# 0.net
KiCad netlist of a schematic drawn in Altium Designer
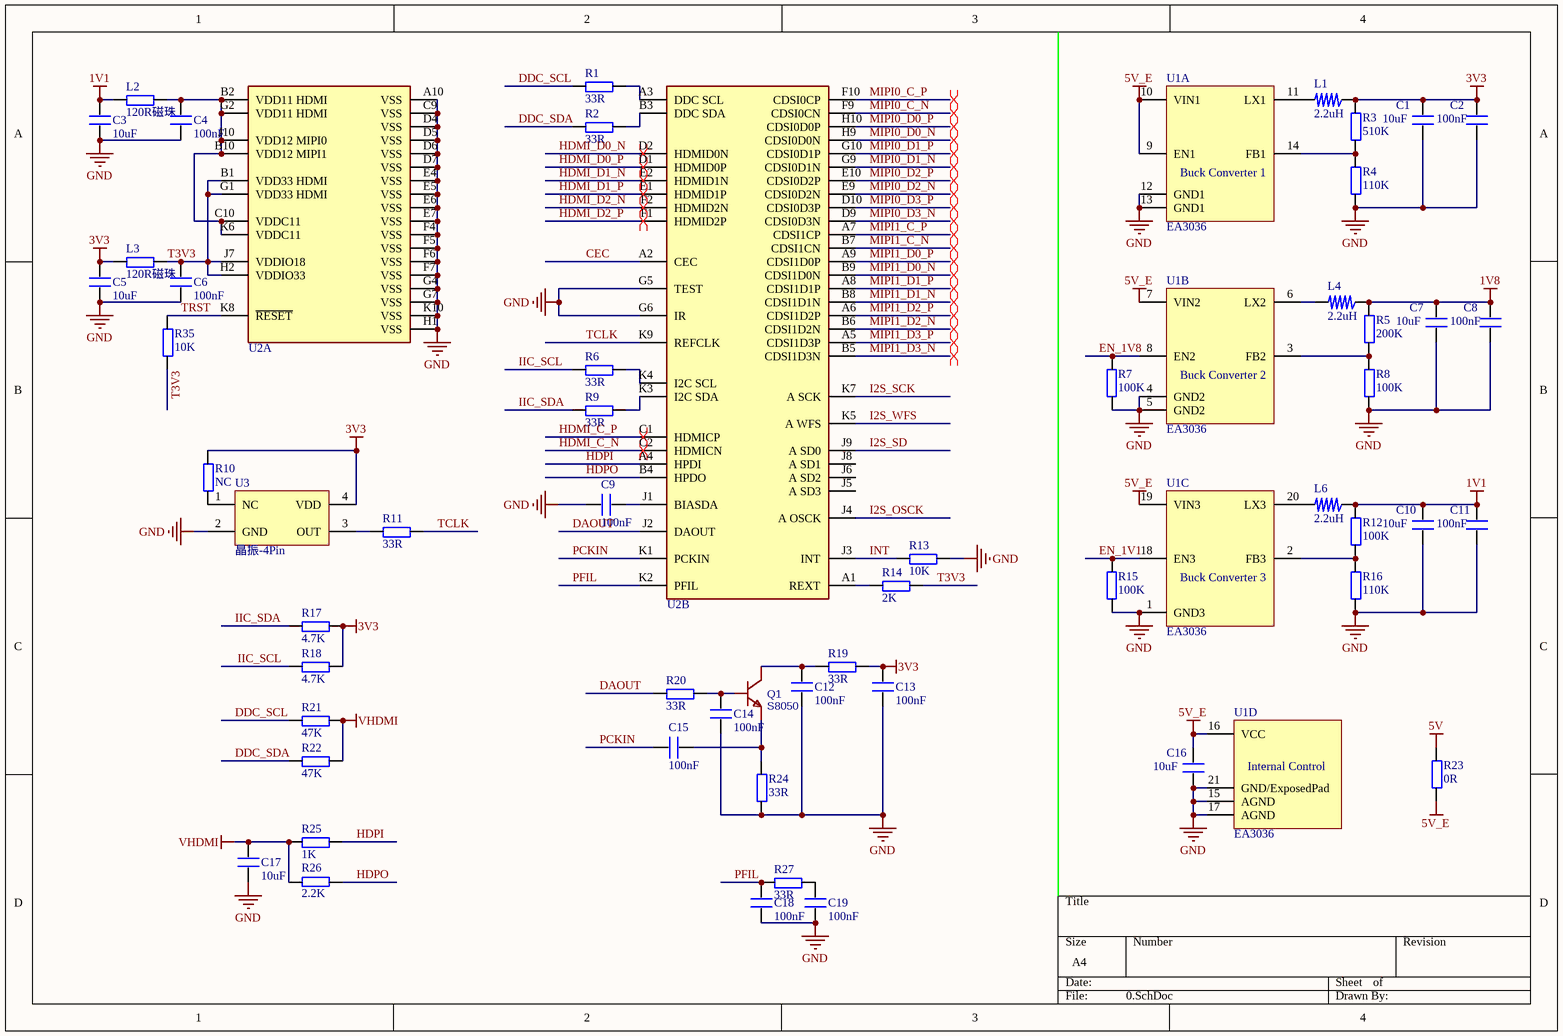
[diagram p0: 0.SchDoc]

(export (version "E")
  (design (tool "Eeschema 10.0.6"))
  (components
    (comp (ref "C1") (value "10uF") (footprint "0603_CAP") (libsource (lib "STM32F429核心板封装库") (part "C")))
    (comp (ref "C2") (value "100nF") (footprint "0603_CAP") (libsource (lib "STM32F429核心板封装库") (part "C")))
    (comp (ref "C3") (value "10uF") (footprint "0603_CAP") (libsource (lib "阿波罗STM32F4&F7底板封装库") (part "C")))
    (comp (ref "C4") (value "100nF") (footprint "0603_CAP") (libsource (lib "阿波罗STM32F4&F7底板封装库") (part "C")))
    (comp (ref "C5") (value "10uF") (footprint "0603_CAP") (libsource (lib "阿波罗STM32F4&F7底板封装库") (part "C")))
    (comp (ref "C6") (value "100nF") (footprint "0603_CAP") (libsource (lib "阿波罗STM32F4&F7底板封装库") (part "C")))
    (comp (ref "C7") (value "10uF") (footprint "0603_CAP") (libsource (lib "STM32F429核心板封装库") (part "C")))
    (comp (ref "C8") (value "100nF") (footprint "0603_CAP") (libsource (lib "STM32F429核心板封装库") (part "C")))
    (comp (ref "C9") (value "100nF") (footprint "0603_CAP") (libsource (lib "阿波罗STM32F4&F7底板封装库") (part "C")))
    (comp (ref "C10") (value "10uF") (footprint "0603_CAP") (libsource (lib "STM32F429核心板封装库") (part "C")))
    (comp (ref "C11") (value "100nF") (footprint "0603_CAP") (libsource (lib "STM32F429核心板封装库") (part "C")))
    (comp (ref "C12")
      (value "100nF")
      (footprint "0603_CAP")
      (libsource (lib "阿波罗STM32F4&F7底板封装库") (part "C"))
    )
    (comp (ref "C13")
      (value "100nF")
      (footprint "0603_CAP")
      (libsource (lib "阿波罗STM32F4&F7底板封装库") (part "C"))
    )
    (comp (ref "C14")
      (value "100nF")
      (footprint "0603_CAP")
      (libsource (lib "阿波罗STM32F4&F7底板封装库") (part "C"))
    )
    (comp (ref "C15")
      (value "100nF")
      (footprint "0603_CAP")
      (libsource (lib "阿波罗STM32F4&F7底板封装库") (part "C"))
    )
    (comp (ref "C16") (value "10uF") (footprint "0603_CAP") (libsource (lib "STM32F429核心板封装库") (part "C")))
    (comp (ref "C17") (value "10uF") (footprint "0603_CAP") (libsource (lib "阿波罗STM32F4&F7底板封装库") (part "C")))
    (comp (ref "C18")
      (value "100nF")
      (footprint "0603_CAP")
      (libsource (lib "阿波罗STM32F4&F7底板封装库") (part "C"))
    )
    (comp (ref "C19")
      (value "100nF")
      (footprint "0603_CAP")
      (libsource (lib "阿波罗STM32F4&F7底板封装库") (part "C"))
    )
    (comp (ref "L1")
      (value "2.2uH")
      (footprint "2520-L")
      (libsource (lib "阿波罗STM32F4&F7底板封装库") (part "L_SOP"))
    )
    (comp (ref "L2") (value "120R磁珠") (footprint "0603_RES") (libsource (lib "STM32F429核心板封装库") (part "R")))
    (comp (ref "L3") (value "120R磁珠") (footprint "0603_RES") (libsource (lib "STM32F429核心板封装库") (part "R")))
    (comp (ref "L4")
      (value "2.2uH")
      (footprint "2520-L")
      (libsource (lib "阿波罗STM32F4&F7底板封装库") (part "L_SOP"))
    )
    (comp (ref "L6")
      (value "2.2uH")
      (footprint "2520-L")
      (libsource (lib "阿波罗STM32F4&F7底板封装库") (part "L_SOP"))
    )
    (comp (ref "Q1")
      (value "S8050")
      (footprint "SOT-23-3_L2.9-W1.3-P1.90-LS2.4-BR")
      (fields (field (name "BOM_SUPPLIER PART") "C779775") (field (name "CONTRIBUTOR") "LCSC"))
      (libsource (lib "altium-import") (part "root_0_S8050_C779775_"))
    )
    (comp (ref "R1") (value "33R") (footprint "0603_RES") (libsource (lib "STM32F429核心板封装库") (part "R")))
    (comp (ref "R2") (value "33R") (footprint "0603_RES") (libsource (lib "STM32F429核心板封装库") (part "R")))
    (comp (ref "R3") (value "510K") (footprint "0603_RES") (libsource (lib "STM32F429核心板封装库") (part "R")))
    (comp (ref "R4") (value "110K") (footprint "0603_RES") (libsource (lib "STM32F429核心板封装库") (part "R")))
    (comp (ref "R5") (value "200K") (footprint "0603_RES") (libsource (lib "STM32F429核心板封装库") (part "R")))
    (comp (ref "R6") (value "33R") (footprint "0603_RES") (libsource (lib "STM32F429核心板封装库") (part "R")))
    (comp (ref "R7") (value "100K") (footprint "0603_RES") (libsource (lib "STM32F429核心板封装库") (part "R")))
    (comp (ref "R8") (value "100K") (footprint "0603_RES") (libsource (lib "STM32F429核心板封装库") (part "R")))
    (comp (ref "R9") (value "33R") (footprint "0603_RES") (libsource (lib "STM32F429核心板封装库") (part "R")))
    (comp (ref "R10") (value "NC") (footprint "0603_RES") (libsource (lib "STM32F429核心板封装库") (part "R")))
    (comp (ref "R11") (value "33R") (footprint "0603_RES") (libsource (lib "STM32F429核心板封装库") (part "R")))
    (comp (ref "R12") (value "100K") (footprint "0603_RES") (libsource (lib "STM32F429核心板封装库") (part "R")))
    (comp (ref "R13") (value "10K") (footprint "0603_RES") (libsource (lib "STM32F429核心板封装库") (part "R")))
    (comp (ref "R14") (value "2K") (footprint "0603_RES") (libsource (lib "STM32F429核心板封装库") (part "R")))
    (comp (ref "R15") (value "100K") (footprint "0603_RES") (libsource (lib "STM32F429核心板封装库") (part "R")))
    (comp (ref "R16") (value "110K") (footprint "0603_RES") (libsource (lib "STM32F429核心板封装库") (part "R")))
    (comp (ref "R17") (value "4.7K") (footprint "0603_RES") (libsource (lib "STM32F429核心板封装库") (part "R")))
    (comp (ref "R18") (value "4.7K") (footprint "0603_RES") (libsource (lib "STM32F429核心板封装库") (part "R")))
    (comp (ref "R19") (value "33R") (footprint "0603_RES") (libsource (lib "STM32F429核心板封装库") (part "R")))
    (comp (ref "R20") (value "33R") (footprint "0603_RES") (libsource (lib "STM32F429核心板封装库") (part "R")))
    (comp (ref "R21") (value "47K") (footprint "0603_RES") (libsource (lib "STM32F429核心板封装库") (part "R")))
    (comp (ref "R22") (value "47K") (footprint "0603_RES") (libsource (lib "STM32F429核心板封装库") (part "R")))
    (comp (ref "R23") (value "0R") (footprint "0603_RES") (libsource (lib "STM32F429核心板封装库") (part "R")))
    (comp (ref "R24") (value "33R") (footprint "0603_RES") (libsource (lib "STM32F429核心板封装库") (part "R")))
    (comp (ref "R25") (value "1K") (footprint "0603_RES") (libsource (lib "STM32F429核心板封装库") (part "R")))
    (comp (ref "R26") (value "2.2K") (footprint "0603_RES") (libsource (lib "STM32F429核心板封装库") (part "R")))
    (comp (ref "R27") (value "33R") (footprint "0603_RES") (libsource (lib "STM32F429核心板封装库") (part "R")))
    (comp (ref "R35") (value "10K") (footprint "0603_RES") (libsource (lib "STM32F429核心板封装库") (part "R")))
    (comp (ref "U1") (value "EA3036") (footprint "QFN-20") (libsource (lib "mLib") (part "EA3036")))
    (comp (ref "U2")
      (value "TC358870XBG")
      (footprint "BGA80_7*7_TC358870XBG")
      (libsource (lib "mLib") (part "TC358870XBG"))
    )
    (comp (ref "U3")
      (value "晶振-4Pin")
      (footprint "晶振2520")
      (description "5032 有源")
      (libsource (lib "mLib") (part "晶振-4Pin"))
    )
  )
  (nets
    (net (code "1") (name "/CEC") (class "Default")
      (node (ref "U2") (pin "A2") (pinfunction "CEC_A2") (pintype "passive"))
    )
    (net (code "2") (name "/DAOUT") (class "Default")
      (node (ref "R20") (pin "1") (pintype "passive"))
      (node (ref "U2") (pin "J2") (pinfunction "DAOUT_J2") (pintype "passive"))
    )
    (net (code "3") (name "/DDC_SCL") (class "Default")
      (node (ref "R1") (pin "1") (pintype "passive"))
      (node (ref "R21") (pin "1") (pintype "passive"))
    )
    (net (code "4") (name "/DDC_SDA") (class "Default")
      (node (ref "R2") (pin "1") (pintype "passive"))
      (node (ref "R22") (pin "1") (pintype "passive"))
    )
    (net (code "5") (name "/EN_1V1") (class "Default")
      (node (ref "R15") (pin "1") (pintype "passive"))
      (node (ref "U1") (pin "18") (pinfunction "EN3_18") (pintype "passive"))
    )
    (net (code "6") (name "/EN_1V8") (class "Default")
      (node (ref "R7") (pin "1") (pintype "passive"))
      (node (ref "U1") (pin "8") (pinfunction "EN2_8") (pintype "passive"))
    )
    (net (code "7") (name "/HDMI_C_N") (class "Default")
      (node (ref "U2") (pin "C2") (pinfunction "HDMICN_C2") (pintype "passive"))
    )
    (net (code "8") (name "/HDMI_C_P") (class "Default")
      (node (ref "U2") (pin "C1") (pinfunction "HDMICP_C1") (pintype "passive"))
    )
    (net (code "9") (name "/HDMI_D0_N") (class "Default")
      (node (ref "U2") (pin "D2") (pinfunction "HDMID0N_D2") (pintype "passive"))
    )
    (net (code "10") (name "/HDMI_D0_P") (class "Default")
      (node (ref "U2") (pin "D1") (pinfunction "HDMID0P_D1") (pintype "passive"))
    )
    (net (code "11") (name "/HDMI_D1_N") (class "Default")
      (node (ref "U2") (pin "E2") (pinfunction "HDMID1N_E2") (pintype "passive"))
    )
    (net (code "12") (name "/HDMI_D1_P") (class "Default")
      (node (ref "U2") (pin "E1") (pinfunction "HDMID1P_E1") (pintype "passive"))
    )
    (net (code "13") (name "/HDMI_D2_N") (class "Default")
      (node (ref "U2") (pin "F2") (pinfunction "HDMID2N_F2") (pintype "passive"))
    )
    (net (code "14") (name "/HDMI_D2_P") (class "Default")
      (node (ref "U2") (pin "F1") (pinfunction "HDMID2P_F1") (pintype "passive"))
    )
    (net (code "15") (name "/HDPI") (class "Default")
      (node (ref "R25") (pin "2") (pintype "passive"))
      (node (ref "U2") (pin "A4") (pinfunction "HPDI_A4") (pintype "passive"))
    )
    (net (code "16") (name "/HDPO") (class "Default")
      (node (ref "R26") (pin "1") (pintype "passive"))
      (node (ref "U2") (pin "B4") (pinfunction "HPDO_B4") (pintype "passive"))
    )
    (net (code "17") (name "/I2S_OSCK") (class "Default")
      (node (ref "U2") (pin "J4") (pinfunction "A_OSCK_J4") (pintype "passive"))
    )
    (net (code "18") (name "/I2S_SCK") (class "Default")
      (node (ref "U2") (pin "K7") (pinfunction "A_SCK_K7") (pintype "passive"))
    )
    (net (code "19") (name "/I2S_SD") (class "Default")
      (node (ref "U2") (pin "J9") (pinfunction "A_SD0_J9") (pintype "passive"))
    )
    (net (code "20") (name "/I2S_WFS") (class "Default")
      (node (ref "U2") (pin "K5") (pinfunction "A_WFS_K5") (pintype "passive"))
    )
    (net (code "21") (name "/IIC_SCL") (class "Default")
      (node (ref "R18") (pin "1") (pintype "passive"))
      (node (ref "R6") (pin "1") (pintype "passive"))
    )
    (net (code "22") (name "/IIC_SDA") (class "Default")
      (node (ref "R17") (pin "1") (pintype "passive"))
      (node (ref "R9") (pin "1") (pintype "passive"))
    )
    (net (code "23") (name "/INT") (class "Default")
      (node (ref "R13") (pin "1") (pintype "passive"))
      (node (ref "U2") (pin "J3") (pinfunction "INT_J3") (pintype "passive"))
    )
    (net (code "24") (name "/MIPI0_C_N") (class "Default")
      (node (ref "U2") (pin "F9") (pinfunction "CDSI0CN_F9") (pintype "passive"))
    )
    (net (code "25") (name "/MIPI0_C_P") (class "Default")
      (node (ref "U2") (pin "F10") (pinfunction "CDSI0CP_F10") (pintype "passive"))
    )
    (net (code "26") (name "/MIPI0_D0_N") (class "Default")
      (node (ref "U2") (pin "H9") (pinfunction "CDSI0D0N_H9") (pintype "passive"))
    )
    (net (code "27") (name "/MIPI0_D0_P") (class "Default")
      (node (ref "U2") (pin "H10") (pinfunction "CDSI0D0P_H10") (pintype "passive"))
    )
    (net (code "28") (name "/MIPI0_D1_N") (class "Default")
      (node (ref "U2") (pin "G9") (pinfunction "CDSI0D1N_G9") (pintype "passive"))
    )
    (net (code "29") (name "/MIPI0_D1_P") (class "Default")
      (node (ref "U2") (pin "G10") (pinfunction "CDSI0D1P_G10") (pintype "passive"))
    )
    (net (code "30") (name "/MIPI0_D2_N") (class "Default")
      (node (ref "U2") (pin "E9") (pinfunction "CDSI0D2N_E9") (pintype "passive"))
    )
    (net (code "31") (name "/MIPI0_D2_P") (class "Default")
      (node (ref "U2") (pin "E10") (pinfunction "CDSI0D2P_E10") (pintype "passive"))
    )
    (net (code "32") (name "/MIPI0_D3_N") (class "Default")
      (node (ref "U2") (pin "D9") (pinfunction "CDSI0D3N_D9") (pintype "passive"))
    )
    (net (code "33") (name "/MIPI0_D3_P") (class "Default")
      (node (ref "U2") (pin "D10") (pinfunction "CDSI0D3P_D10") (pintype "passive"))
    )
    (net (code "34") (name "/MIPI1_C_N") (class "Default")
      (node (ref "U2") (pin "B7") (pinfunction "CDSI1CN_B7") (pintype "passive"))
    )
    (net (code "35") (name "/MIPI1_C_P") (class "Default")
      (node (ref "U2") (pin "A7") (pinfunction "CDSI1CP_A7") (pintype "passive"))
    )
    (net (code "36") (name "/MIPI1_D0_N") (class "Default")
      (node (ref "U2") (pin "B9") (pinfunction "CDSI1D0N_B9") (pintype "passive"))
    )
    (net (code "37") (name "/MIPI1_D0_P") (class "Default")
      (node (ref "U2") (pin "A9") (pinfunction "CDSI1D0P_A9") (pintype "passive"))
    )
    (net (code "38") (name "/MIPI1_D1_N") (class "Default")
      (node (ref "U2") (pin "B8") (pinfunction "CDSI1D1N_B8") (pintype "passive"))
    )
    (net (code "39") (name "/MIPI1_D1_P") (class "Default")
      (node (ref "U2") (pin "A8") (pinfunction "CDSI1D1P_A8") (pintype "passive"))
    )
    (net (code "40") (name "/MIPI1_D2_N") (class "Default")
      (node (ref "U2") (pin "B6") (pinfunction "CDSI1D2N_B6") (pintype "passive"))
    )
    (net (code "41") (name "/MIPI1_D2_P") (class "Default")
      (node (ref "U2") (pin "A6") (pinfunction "CDSI1D2P_A6") (pintype "passive"))
    )
    (net (code "42") (name "/MIPI1_D3_N") (class "Default")
      (node (ref "U2") (pin "B5") (pinfunction "CDSI1D3N_B5") (pintype "passive"))
    )
    (net (code "43") (name "/MIPI1_D3_P") (class "Default")
      (node (ref "U2") (pin "A5") (pinfunction "CDSI1D3P_A5") (pintype "passive"))
    )
    (net (code "44") (name "/PCKIN") (class "Default")
      (node (ref "C15") (pin "2") (pintype "passive"))
      (node (ref "U2") (pin "K1") (pinfunction "PCKIN_K1") (pintype "passive"))
    )
    (net (code "45") (name "/PFIL") (class "Default")
      (node (ref "C18") (pin "2") (pintype "passive"))
      (node (ref "R27") (pin "1") (pintype "passive"))
      (node (ref "U2") (pin "K2") (pinfunction "PFIL_K2") (pintype "passive"))
    )
    (net (code "46") (name "/T3V3") (class "Default")
      (node (ref "C6") (pin "1") (pintype "passive"))
      (node (ref "L3") (pin "2") (pintype "passive"))
      (node (ref "R14") (pin "2") (pintype "passive"))
      (node (ref "R35") (pin "1") (pintype "passive"))
      (node (ref "U2") (pin "B1") (pinfunction "VDD33_HDMI_B1") (pintype "passive"))
      (node (ref "U2") (pin "G1") (pinfunction "VDD33_HDMI_G1") (pintype "passive"))
      (node (ref "U2") (pin "H2") (pinfunction "VDDIO33_H2") (pintype "passive"))
      (node (ref "U2") (pin "J7") (pinfunction "VDDIO18_J7") (pintype "passive"))
    )
    (net (code "47") (name "/TCLK") (class "Default")
      (node (ref "R11") (pin "2") (pintype "passive"))
      (node (ref "U2") (pin "K9") (pinfunction "REFCLK_K9") (pintype "passive"))
    )
    (net (code "48") (name "/TRST") (class "Default")
      (node (ref "R35") (pin "2") (pintype "passive"))
      (node (ref "U2") (pin "K8") (pinfunction "~{RESET}_K8") (pintype "passive"))
    )
    (net (code "49") (name "1V1") (class "Default")
      (node (ref "C10") (pin "2") (pintype "passive"))
      (node (ref "C11") (pin "2") (pintype "passive"))
      (node (ref "C3") (pin "1") (pintype "passive"))
      (node (ref "L2") (pin "1") (pintype "passive"))
      (node (ref "L6") (pin "1") (pinfunction "1_1") (pintype "passive"))
      (node (ref "R12") (pin "2") (pintype "passive"))
    )
    (net (code "50") (name "1V8") (class "Default")
      (node (ref "C7") (pin "2") (pintype "passive"))
      (node (ref "C8") (pin "2") (pintype "passive"))
      (node (ref "L4") (pin "1") (pinfunction "1_1") (pintype "passive"))
      (node (ref "R5") (pin "2") (pintype "passive"))
    )
    (net (code "51") (name "3V3") (class "Default")
      (node (ref "C1") (pin "2") (pintype "passive"))
      (node (ref "C13") (pin "2") (pintype "passive"))
      (node (ref "C2") (pin "2") (pintype "passive"))
      (node (ref "C5") (pin "1") (pintype "passive"))
      (node (ref "L1") (pin "1") (pinfunction "1_1") (pintype "passive"))
      (node (ref "L3") (pin "1") (pintype "passive"))
      (node (ref "R10") (pin "2") (pintype "passive"))
      (node (ref "R17") (pin "2") (pintype "passive"))
      (node (ref "R18") (pin "2") (pintype "passive"))
      (node (ref "R19") (pin "2") (pintype "passive"))
      (node (ref "R3") (pin "2") (pintype "passive"))
      (node (ref "U3") (pin "4") (pinfunction "VDD_4") (pintype "passive"))
    )
    (net (code "52") (name "5V") (class "Default") (node (ref "R23") (pin "2") (pintype "passive")))
    (net (code "53") (name "5V_E") (class "Default")
      (node (ref "C16") (pin "2") (pintype "passive"))
      (node (ref "R23") (pin "1") (pintype "passive"))
      (node (ref "U1") (pin "10") (pinfunction "VIN1_10") (pintype "power_in"))
      (node (ref "U1") (pin "16") (pinfunction "VCC_16") (pintype "power_in"))
      (node (ref "U1") (pin "19") (pinfunction "VIN3_19") (pintype "power_in"))
      (node (ref "U1") (pin "7") (pinfunction "VIN2_7") (pintype "power_in"))
      (node (ref "U1") (pin "9") (pinfunction "EN1_9") (pintype "passive"))
    )
    (net (code "54") (name "GND") (class "Default")
      (node (ref "C1") (pin "1") (pintype "passive"))
      (node (ref "C10") (pin "1") (pintype "passive"))
      (node (ref "C11") (pin "1") (pintype "passive"))
      (node (ref "C12") (pin "1") (pintype "passive"))
      (node (ref "C13") (pin "1") (pintype "passive"))
      (node (ref "C14") (pin "1") (pintype "passive"))
      (node (ref "C16") (pin "1") (pintype "passive"))
      (node (ref "C17") (pin "1") (pintype "passive"))
      (node (ref "C18") (pin "1") (pintype "passive"))
      (node (ref "C19") (pin "1") (pintype "passive"))
      (node (ref "C2") (pin "1") (pintype "passive"))
      (node (ref "C3") (pin "2") (pintype "passive"))
      (node (ref "C4") (pin "2") (pintype "passive"))
      (node (ref "C5") (pin "2") (pintype "passive"))
      (node (ref "C6") (pin "2") (pintype "passive"))
      (node (ref "C7") (pin "1") (pintype "passive"))
      (node (ref "C8") (pin "1") (pintype "passive"))
      (node (ref "C9") (pin "1") (pintype "passive"))
      (node (ref "R13") (pin "2") (pintype "passive"))
      (node (ref "R15") (pin "2") (pintype "passive"))
      (node (ref "R16") (pin "1") (pintype "passive"))
      (node (ref "R24") (pin "1") (pintype "passive"))
      (node (ref "R4") (pin "1") (pintype "passive"))
      (node (ref "R7") (pin "2") (pintype "passive"))
      (node (ref "R8") (pin "1") (pintype "passive"))
      (node (ref "U1") (pin "1") (pinfunction "GND3_1") (pintype "power_in"))
      (node (ref "U1") (pin "12") (pinfunction "GND1_12") (pintype "power_in"))
      (node (ref "U1") (pin "13") (pinfunction "GND1_13") (pintype "power_in"))
      (node (ref "U1") (pin "15") (pinfunction "AGND_15") (pintype "power_in"))
      (node (ref "U1") (pin "17") (pinfunction "AGND_17") (pintype "power_in"))
      (node (ref "U1") (pin "21") (pinfunction "GND/ExposedPad_21") (pintype "power_in"))
      (node (ref "U1") (pin "4") (pinfunction "GND2_4") (pintype "power_in"))
      (node (ref "U1") (pin "5") (pinfunction "GND2_5") (pintype "power_in"))
      (node (ref "U2") (pin "A10") (pinfunction "VSS_A10") (pintype "passive"))
      (node (ref "U2") (pin "C9") (pinfunction "VSS_C9") (pintype "passive"))
      (node (ref "U2") (pin "D4") (pinfunction "VSS_D4") (pintype "passive"))
      (node (ref "U2") (pin "D5") (pinfunction "VSS_D5") (pintype "passive"))
      (node (ref "U2") (pin "D6") (pinfunction "VSS_D6") (pintype "passive"))
      (node (ref "U2") (pin "D7") (pinfunction "VSS_D7") (pintype "passive"))
      (node (ref "U2") (pin "E4") (pinfunction "VSS_E4") (pintype "passive"))
      (node (ref "U2") (pin "E5") (pinfunction "VSS_E5") (pintype "passive"))
      (node (ref "U2") (pin "E6") (pinfunction "VSS_E6") (pintype "passive"))
      (node (ref "U2") (pin "E7") (pinfunction "VSS_E7") (pintype "passive"))
      (node (ref "U2") (pin "F4") (pinfunction "VSS_F4") (pintype "passive"))
      (node (ref "U2") (pin "F5") (pinfunction "VSS_F5") (pintype "passive"))
      (node (ref "U2") (pin "F6") (pinfunction "VSS_F6") (pintype "passive"))
      (node (ref "U2") (pin "F7") (pinfunction "VSS_F7") (pintype "passive"))
      (node (ref "U2") (pin "G4") (pinfunction "VSS_G4") (pintype "passive"))
      (node (ref "U2") (pin "G5") (pinfunction "TEST_G5") (pintype "passive"))
      (node (ref "U2") (pin "G6") (pinfunction "IR_G6") (pintype "passive"))
      (node (ref "U2") (pin "G7") (pinfunction "VSS_G7") (pintype "passive"))
      (node (ref "U2") (pin "H1") (pinfunction "VSS_H1") (pintype "passive"))
      (node (ref "U2") (pin "K10") (pinfunction "VSS_K10") (pintype "passive"))
      (node (ref "U3") (pin "2") (pinfunction "GND_2") (pintype "passive"))
    )
    (net (code "55") (name "Net-(C19-Pad2)") (class "Default")
      (node (ref "C19") (pin "2") (pintype "passive"))
      (node (ref "R27") (pin "2") (pintype "passive"))
    )
    (net (code "56") (name "Net-(Q1-B)") (class "Default")
      (node (ref "C14") (pin "2") (pintype "passive"))
      (node (ref "Q1") (pin "1") (pinfunction "B_1") (pintype "passive"))
      (node (ref "R20") (pin "2") (pintype "passive"))
    )
    (net (code "57") (name "Net-(Q1-C)") (class "Default")
      (node (ref "C12") (pin "2") (pintype "passive"))
      (node (ref "Q1") (pin "3") (pinfunction "C_3") (pintype "passive"))
      (node (ref "R19") (pin "1") (pintype "passive"))
    )
    (net (code "58") (name "Net-(Q1-E)") (class "Default")
      (node (ref "C15") (pin "1") (pintype "passive"))
      (node (ref "Q1") (pin "2") (pinfunction "E_2") (pintype "passive"))
      (node (ref "R24") (pin "2") (pintype "passive"))
    )
    (net (code "59") (name "Net-(U1A-FB1)") (class "Default")
      (node (ref "R3") (pin "1") (pintype "passive"))
      (node (ref "R4") (pin "2") (pintype "passive"))
      (node (ref "U1") (pin "14") (pinfunction "FB1_14") (pintype "passive"))
    )
    (net (code "60") (name "Net-(U1A-LX1)") (class "Default")
      (node (ref "L1") (pin "2") (pinfunction "2_2") (pintype "passive"))
      (node (ref "U1") (pin "11") (pinfunction "LX1_11") (pintype "passive"))
    )
    (net (code "61") (name "Net-(U1B-FB2)") (class "Default")
      (node (ref "R5") (pin "1") (pintype "passive"))
      (node (ref "R8") (pin "2") (pintype "passive"))
      (node (ref "U1") (pin "3") (pinfunction "FB2_3") (pintype "passive"))
    )
    (net (code "62") (name "Net-(U1B-LX2)") (class "Default")
      (node (ref "L4") (pin "2") (pinfunction "2_2") (pintype "passive"))
      (node (ref "U1") (pin "6") (pinfunction "LX2_6") (pintype "passive"))
    )
    (net (code "63") (name "Net-(U1C-FB3)") (class "Default")
      (node (ref "R12") (pin "1") (pintype "passive"))
      (node (ref "R16") (pin "2") (pintype "passive"))
      (node (ref "U1") (pin "2") (pinfunction "FB3_2") (pintype "passive"))
    )
    (net (code "64") (name "Net-(U1C-LX3)") (class "Default")
      (node (ref "L6") (pin "2") (pinfunction "2_2") (pintype "passive"))
      (node (ref "U1") (pin "20") (pinfunction "LX3_20") (pintype "passive"))
    )
    (net (code "65") (name "Net-(U2A-VDD12_MIPI0)") (class "Default")
      (node (ref "C4") (pin "1") (pintype "passive"))
      (node (ref "L2") (pin "2") (pintype "passive"))
      (node (ref "U2") (pin "B10") (pinfunction "VDD12_MIPI1_B10") (pintype "passive"))
      (node (ref "U2") (pin "B2") (pinfunction "VDD11_HDMI_B2") (pintype "passive"))
      (node (ref "U2") (pin "C10") (pinfunction "VDDC11_C10") (pintype "passive"))
      (node (ref "U2") (pin "G2") (pinfunction "VDD11_HDMI_G2") (pintype "passive"))
      (node (ref "U2") (pin "J10") (pinfunction "VDD12_MIPI0_J10") (pintype "passive"))
      (node (ref "U2") (pin "K6") (pinfunction "VDDC11_K6") (pintype "passive"))
    )
    (net (code "66") (name "Net-(U2B-BIASDA)") (class "Default")
      (node (ref "C9") (pin "2") (pintype "passive"))
      (node (ref "U2") (pin "J1") (pinfunction "BIASDA_J1") (pintype "passive"))
    )
    (net (code "67") (name "Net-(U2B-DDC_SCL)") (class "Default")
      (node (ref "R1") (pin "2") (pintype "passive"))
      (node (ref "U2") (pin "A3") (pinfunction "DDC_SCL_A3") (pintype "passive"))
    )
    (net (code "68") (name "Net-(U2B-DDC_SDA)") (class "Default")
      (node (ref "R2") (pin "2") (pintype "passive"))
      (node (ref "U2") (pin "B3") (pinfunction "DDC_SDA_B3") (pintype "passive"))
    )
    (net (code "69") (name "Net-(U2B-I2C_SCL)") (class "Default")
      (node (ref "R6") (pin "2") (pintype "passive"))
      (node (ref "U2") (pin "K4") (pinfunction "I2C_SCL_K4") (pintype "passive"))
    )
    (net (code "70") (name "Net-(U2B-I2C_SDA)") (class "Default")
      (node (ref "R9") (pin "2") (pintype "passive"))
      (node (ref "U2") (pin "K3") (pinfunction "I2C_SDA_K3") (pintype "passive"))
    )
    (net (code "71") (name "Net-(U2B-REXT)") (class "Default")
      (node (ref "R14") (pin "1") (pintype "passive"))
      (node (ref "U2") (pin "A1") (pinfunction "REXT_A1") (pintype "passive"))
    )
    (net (code "72") (name "Net-(U3-NC)") (class "Default")
      (node (ref "R10") (pin "1") (pintype "passive"))
      (node (ref "U3") (pin "1") (pinfunction "NC_1") (pintype "passive"))
    )
    (net (code "73") (name "Net-(U3-OUT)") (class "Default")
      (node (ref "R11") (pin "1") (pintype "passive"))
      (node (ref "U3") (pin "3") (pinfunction "OUT_3") (pintype "passive"))
    )
    (net (code "74") (name "VHDMI") (class "Default")
      (node (ref "C17") (pin "2") (pintype "passive"))
      (node (ref "R21") (pin "2") (pintype "passive"))
      (node (ref "R22") (pin "2") (pintype "passive"))
      (node (ref "R25") (pin "1") (pintype "passive"))
      (node (ref "R26") (pin "2") (pintype "passive"))
    )
    (net (code "75") (name "unconnected-(U2B-A_SD1-PadJ8)") (class "Default")
      (node (ref "U2") (pin "J8") (pinfunction "A_SD1_J8") (pintype "passive"))
    )
    (net (code "76") (name "unconnected-(U2B-A_SD2-PadJ6)") (class "Default")
      (node (ref "U2") (pin "J6") (pinfunction "A_SD2_J6") (pintype "passive"))
    )
    (net (code "77") (name "unconnected-(U2B-A_SD3-PadJ5)") (class "Default")
      (node (ref "U2") (pin "J5") (pinfunction "A_SD3_J5") (pintype "passive"))
    )
  )
)
